# IMU.net
KiCad netlist of a schematic drawn in Altium Designer
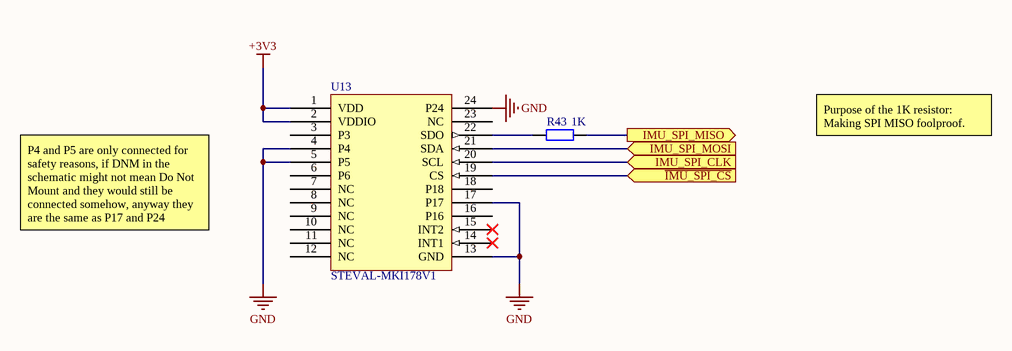
[diagram p0: IMU.SchDoc]

(export (version "E")
  (design (tool "Eeschema 10.0.6"))
  (components
    (comp (ref "R43")
      (value "1K")
      (footprint "FP_0805_RES")
      (description "Resistor")
      (fields (field (name "TOLERANCE") "5%") (field (name "POWER") "0.125W"))
      (libsource (lib "LKBulls2023") (part "RES"))
    )
    (comp (ref "U13")
      (value "STEVAL-MKI178V1")
      (footprint "FP_STEVAL_IMU")
      (description "Adapter board for LSM6DS3H 3D digital accelerometer and 3D digital gyroscope , SPI/I2C interface")
      (libsource (lib "LKBulls2023") (part "STEVAL-MKI178V1"))
    )
  )
  (nets
    (net (code "1") (name "+3V3") (class "Default")
      (node (ref "U13") (pin "1") (pinfunction "VDD_1") (pintype "passive"))
      (node (ref "U13") (pin "2") (pinfunction "VDDIO_2") (pintype "passive"))
    )
    (net (code "2") (name "/IMU_SPI_CLK") (class "Default")
      (node (ref "U13") (pin "20") (pinfunction "SCL_20") (pintype "input"))
    )
    (net (code "3") (name "/IMU_SPI_MISO") (class "Default")
      (node (ref "R43") (pin "2") (pinfunction "2_2") (pintype "passive"))
    )
    (net (code "4") (name "/IMU_SPI_MOSI") (class "Default")
      (node (ref "U13") (pin "21") (pinfunction "SDA_21") (pintype "input"))
    )
    (net (code "5") (name "/~{IMU_SPI_CS}") (class "Default")
      (node (ref "U13") (pin "19") (pinfunction "CS_19") (pintype "input"))
    )
    (net (code "6") (name "GND") (class "Default")
      (node (ref "U13") (pin "13") (pinfunction "GND_13") (pintype "passive"))
      (node (ref "U13") (pin "17") (pinfunction "P17_17") (pintype "passive"))
      (node (ref "U13") (pin "24") (pinfunction "P24_24") (pintype "passive"))
      (node (ref "U13") (pin "4") (pinfunction "P4_4") (pintype "passive"))
      (node (ref "U13") (pin "5") (pinfunction "P5_5") (pintype "passive"))
    )
    (net (code "7") (name "Net-(U13-SDO)") (class "Default")
      (node (ref "R43") (pin "1") (pinfunction "1_1") (pintype "passive"))
      (node (ref "U13") (pin "22") (pinfunction "SDO_22") (pintype "output"))
    )
    (net (code "8") (name "unconnected-(U13-INT1-Pad14)") (class "Default")
      (node (ref "U13") (pin "14") (pinfunction "INT1_14") (pintype "input+no_connect"))
    )
    (net (code "9") (name "unconnected-(U13-INT2-Pad15)") (class "Default")
      (node (ref "U13") (pin "15") (pinfunction "INT2_15") (pintype "input+no_connect"))
    )
    (net (code "10") (name "unconnected-(U13-NC-Pad7)") (class "Default")
      (node (ref "U13") (pin "7") (pinfunction "NC_7") (pintype "passive"))
    )
    (net (code "11") (name "unconnected-(U13-NC-Pad8)") (class "Default")
      (node (ref "U13") (pin "8") (pinfunction "NC_8") (pintype "passive"))
    )
    (net (code "12") (name "unconnected-(U13-NC-Pad9)") (class "Default")
      (node (ref "U13") (pin "9") (pinfunction "NC_9") (pintype "passive"))
    )
    (net (code "13") (name "unconnected-(U13-NC-Pad10)") (class "Default")
      (node (ref "U13") (pin "10") (pinfunction "NC_10") (pintype "passive"))
    )
    (net (code "14") (name "unconnected-(U13-NC-Pad11)") (class "Default")
      (node (ref "U13") (pin "11") (pinfunction "NC_11") (pintype "passive"))
    )
    (net (code "15") (name "unconnected-(U13-NC-Pad12)") (class "Default")
      (node (ref "U13") (pin "12") (pinfunction "NC_12") (pintype "passive"))
    )
    (net (code "16") (name "unconnected-(U13-NC-Pad23)") (class "Default")
      (node (ref "U13") (pin "23") (pinfunction "NC_23") (pintype "passive"))
    )
    (net (code "17") (name "unconnected-(U13-P3-Pad3)") (class "Default")
      (node (ref "U13") (pin "3") (pinfunction "P3_3") (pintype "passive"))
    )
    (net (code "18") (name "unconnected-(U13-P6-Pad6)") (class "Default")
      (node (ref "U13") (pin "6") (pinfunction "P6_6") (pintype "passive"))
    )
    (net (code "19") (name "unconnected-(U13-P16-Pad16)") (class "Default")
      (node (ref "U13") (pin "16") (pinfunction "P16_16") (pintype "passive"))
    )
    (net (code "20") (name "unconnected-(U13-P18-Pad18)") (class "Default")
      (node (ref "U13") (pin "18") (pinfunction "P18_18") (pintype "passive"))
    )
  )
)
